# CLK.net
KiCad netlist of a schematic drawn in Altium Designer
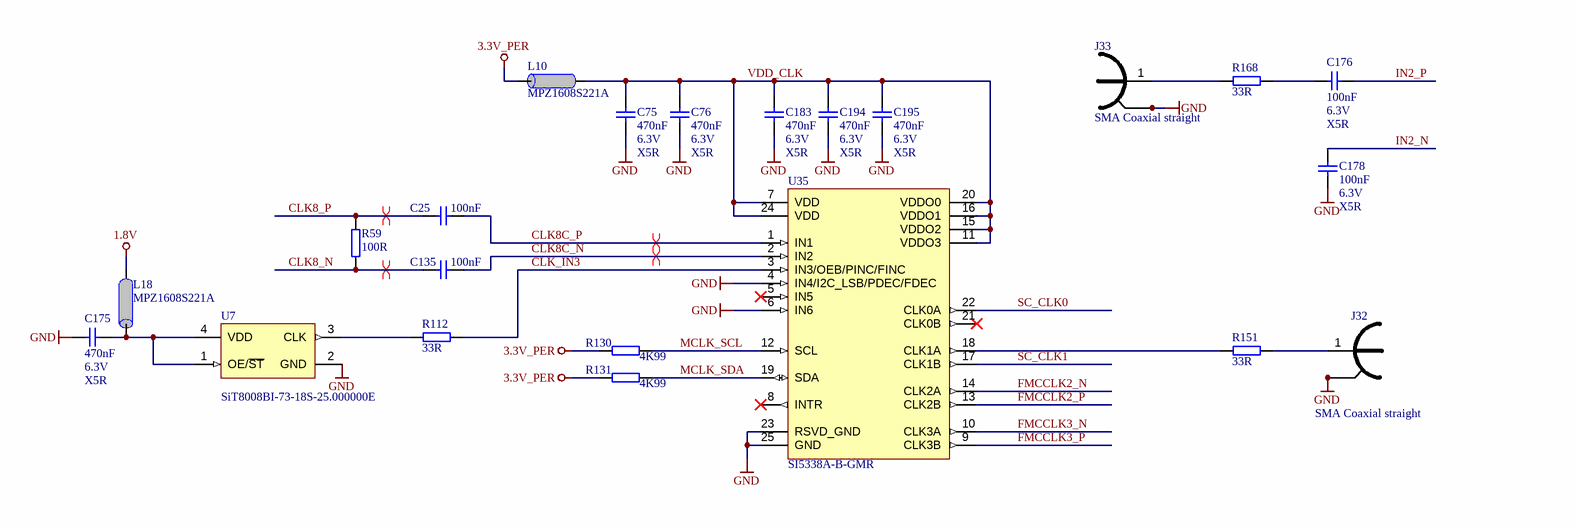
[diagram p0: CLK.schdoc]

(export (version "E")
  (design (tool "Eeschema 10.0.6"))
  (components
    (comp (ref "C25")
      (value "100nF")
      (footprint "CAPC0603X33N")
      (description "KON 100nF 6.3V X5R SMD 10%")
      (fields (field (name "VOLTAGE") "6.3V") (field (name "TOLERANCE") "10%"))
      (libsource (lib "TE") (part "CAP-NP"))
    )
    (comp (ref "C75")
      (value "470nF")
      (footprint "CAPC1005X55N")
      (description "KON 470nF 6,3V X5R SMD")
      (fields (field (name "VOLTAGE") "6.3V") (field (name "TECHNOLOGY") "X5R"))
      (libsource (lib "TE") (part "CAP-NP"))
    )
    (comp (ref "C76")
      (value "470nF")
      (footprint "CAPC1005X55N")
      (description "KON 470nF 6,3V X5R SMD")
      (fields (field (name "VOLTAGE") "6.3V") (field (name "TECHNOLOGY") "X5R"))
      (libsource (lib "TE") (part "CAP-NP"))
    )
    (comp (ref "C135")
      (value "100nF")
      (footprint "CAPC0603X33N")
      (description "KON 100nF 6.3V X5R SMD 10%")
      (fields (field (name "VOLTAGE") "6.3V") (field (name "TOLERANCE") "10%"))
      (libsource (lib "TE") (part "CAP-NP"))
    )
    (comp (ref "C175")
      (value "470nF")
      (footprint "CAPC1005X55N")
      (description "KON 470nF 6,3V X5R SMD")
      (fields (field (name "VOLTAGE") "6.3V") (field (name "TECHNOLOGY") "X5R"))
      (libsource (lib "TE") (part "CAP-NP"))
    )
    (comp (ref "C176")
      (value "100nF")
      (footprint "CAPC0603X33N")
      (description "KON 100nF 6.3V X5R SMD 10%")
      (fields
        (field (name "VOLTAGE") "6.3V")
        (field (name "TECHNOLOGY") "X5R")
        (field (name "TOLERANCE") "10%")
      )
      (libsource (lib "TE") (part "CAP-NP"))
    )
    (comp (ref "C178")
      (value "100nF")
      (footprint "CAPC0603X33N")
      (description "KON 100nF 6.3V X5R SMD 10%")
      (fields
        (field (name "VOLTAGE") "6.3V")
        (field (name "TECHNOLOGY") "X5R")
        (field (name "TOLERANCE") "10%")
      )
      (libsource (lib "TE") (part "CAP-NP"))
    )
    (comp (ref "C183")
      (value "470nF")
      (footprint "CAPC1005X55N")
      (description "KON 470nF 6,3V X5R SMD")
      (fields (field (name "VOLTAGE") "6.3V") (field (name "TECHNOLOGY") "X5R"))
      (libsource (lib "TE") (part "CAP-NP"))
    )
    (comp (ref "C194")
      (value "470nF")
      (footprint "CAPC1005X55N")
      (description "KON 470nF 6,3V X5R SMD")
      (fields (field (name "VOLTAGE") "6.3V") (field (name "TECHNOLOGY") "X5R"))
      (libsource (lib "TE") (part "CAP-NP"))
    )
    (comp (ref "C195")
      (value "470nF")
      (footprint "CAPC1005X55N")
      (description "KON 470nF 6,3V X5R SMD")
      (fields (field (name "VOLTAGE") "6.3V") (field (name "TECHNOLOGY") "X5R"))
      (libsource (lib "TE") (part "CAP-NP"))
    )
    (comp (ref "J32")
      (value "SMA Coaxial straight")
      (footprint "SMA-R125426000")
      (libsource (lib "") (part "SMA_1"))
    )
    (comp (ref "J33")
      (value "SMA Coaxial straight")
      (footprint "SMA-R125426000")
      (libsource (lib "TE") (part "SMA"))
    )
    (comp (ref "L10")
      (value "MPZ1608S221A")
      (footprint "INDC1608X95N")
      (description "Ferritdurchführung MPZ1608S221A")
      (libsource (lib "TE") (part "Ferritperle"))
    )
    (comp (ref "L18")
      (value "MPZ1608S221A")
      (footprint "INDC1608X95N")
      (description "Ferritdurchführung MPZ1608S221A")
      (libsource (lib "") (part "Ferritperle_1"))
    )
    (comp (ref "R59")
      (value "100R")
      (footprint "RESC1005X40N")
      (description "WID SMD 100R 1% 0,063W")
      (fields (field (name "TOLERANCE") "1%"))
      (libsource (lib "TE") (part "RES"))
    )
    (comp (ref "R112")
      (value "33R")
      (footprint "RESC1005X40N")
      (description "WID SMD 33R 1% 0,063W")
      (fields (field (name "TOLERANCE") "1%"))
      (libsource (lib "TE") (part "RES"))
    )
    (comp (ref "R130")
      (value "4K99")
      (footprint "RESC1005X40N")
      (description "WID SMD 4K99 1% 0,063W")
      (fields (field (name "TOLERANCE") "1%"))
      (libsource (lib "TE") (part "RES"))
    )
    (comp (ref "R131")
      (value "4K99")
      (footprint "RESC1005X40N")
      (description "WID SMD 4K99 1% 0,063W")
      (fields (field (name "TOLERANCE") "1%"))
      (libsource (lib "TE") (part "RES"))
    )
    (comp (ref "R151")
      (value "33R")
      (footprint "RESC1005X40N")
      (description "WID SMD 33R 1% 0,063W")
      (fields (field (name "TOLERANCE") "1%"))
      (libsource (lib "TE") (part "RES"))
    )
    (comp (ref "R168")
      (value "33R")
      (footprint "RESC1005X40N")
      (description "WID SMD 33R 1% 0,063W")
      (fields (field (name "TOLERANCE") "1%"))
      (libsource (lib "TE") (part "RES"))
    )
    (comp (ref "U7")
      (value "SiT8008BI-73-18S-25.000000E")
      (footprint "2016")
      (fields (field (name "VOLTAGE") "1.8V"))
      (libsource (lib "TE") (part "SiT8103"))
    )
    (comp (ref "U35")
      (value "SI5338A-B-GMR")
      (footprint "QFN50P400X400X90-25N")
      (description "SI5338A-B-GM")
      (libsource (lib "TE") (part "SI5338A"))
    )
  )
  (nets
    (net (code "1") (name "/CLK8C_N") (class "Default")
      (node (ref "C135") (pin "2") (pinfunction "2_2") (pintype "passive"))
      (node (ref "U35") (pin "2") (pinfunction "IN2_2") (pintype "input"))
    )
    (net (code "2") (name "/CLK8C_P") (class "Default")
      (node (ref "C25") (pin "2") (pinfunction "2_2") (pintype "passive"))
      (node (ref "U35") (pin "1") (pinfunction "IN1_1") (pintype "input"))
    )
    (net (code "3") (name "/CLK8_N") (class "Default")
      (node (ref "C135") (pin "1") (pinfunction "1_1") (pintype "passive"))
      (node (ref "R59") (pin "2") (pinfunction "2_2") (pintype "passive"))
    )
    (net (code "4") (name "/CLK8_P") (class "Default")
      (node (ref "C25") (pin "1") (pinfunction "1_1") (pintype "passive"))
      (node (ref "R59") (pin "1") (pinfunction "1_1") (pintype "passive"))
    )
    (net (code "5") (name "/CLK_IN3") (class "Default")
      (node (ref "R112") (pin "2") (pinfunction "2_2") (pintype "passive"))
      (node (ref "U35") (pin "3") (pinfunction "IN3/OEB/PINC/FINC_3") (pintype "input"))
    )
    (net (code "6") (name "/FMCCLK2_N") (class "Default")
      (node (ref "U35") (pin "14") (pinfunction "CLK2A_14") (pintype "output"))
    )
    (net (code "7") (name "/FMCCLK2_P") (class "Default")
      (node (ref "U35") (pin "13") (pinfunction "CLK2B_13") (pintype "output"))
    )
    (net (code "8") (name "/FMCCLK3_N") (class "Default")
      (node (ref "U35") (pin "10") (pinfunction "CLK3A_10") (pintype "output"))
    )
    (net (code "9") (name "/FMCCLK3_P") (class "Default")
      (node (ref "U35") (pin "9") (pinfunction "CLK3B_9") (pintype "output"))
    )
    (net (code "10") (name "/IN2_N") (class "Default")
      (node (ref "C178") (pin "2") (pinfunction "2_2") (pintype "passive"))
    )
    (net (code "11") (name "/IN2_P") (class "Default")
      (node (ref "C176") (pin "1") (pinfunction "1_1") (pintype "passive"))
    )
    (net (code "12") (name "/MCLK_SCL") (class "Default")
      (node (ref "R130") (pin "2") (pinfunction "2_2") (pintype "passive"))
      (node (ref "U35") (pin "12") (pinfunction "SCL_12") (pintype "input"))
    )
    (net (code "13") (name "/MCLK_SDA") (class "Default")
      (node (ref "R131") (pin "2") (pinfunction "2_2") (pintype "passive"))
      (node (ref "U35") (pin "19") (pinfunction "SDA_19") (pintype "bidirectional"))
    )
    (net (code "14") (name "/SC_CLK0") (class "Default")
      (node (ref "U35") (pin "22") (pinfunction "CLK0A_22") (pintype "output"))
    )
    (net (code "15") (name "/SC_CLK1") (class "Default")
      (node (ref "U35") (pin "17") (pinfunction "CLK1B_17") (pintype "output"))
    )
    (net (code "16") (name "/VDD_CLK") (class "Default")
      (node (ref "C183") (pin "1") (pinfunction "1_1") (pintype "passive"))
      (node (ref "C194") (pin "1") (pinfunction "1_1") (pintype "passive"))
      (node (ref "C195") (pin "1") (pinfunction "1_1") (pintype "passive"))
      (node (ref "C75") (pin "1") (pinfunction "1_1") (pintype "passive"))
      (node (ref "C76") (pin "1") (pinfunction "1_1") (pintype "passive"))
      (node (ref "L10") (pin "1") (pinfunction "1_1") (pintype "passive"))
      (node (ref "U35") (pin "11") (pinfunction "VDDO3_11") (pintype "power_in"))
      (node (ref "U35") (pin "15") (pinfunction "VDDO2_15") (pintype "power_in"))
      (node (ref "U35") (pin "16") (pinfunction "VDDO1_16") (pintype "power_in"))
      (node (ref "U35") (pin "20") (pinfunction "VDDO0_20") (pintype "power_in"))
      (node (ref "U35") (pin "24") (pinfunction "VDD_24") (pintype "power_in"))
      (node (ref "U35") (pin "7") (pinfunction "VDD_7") (pintype "power_in"))
    )
    (net (code "17") (name "1.8V") (class "Default")
      (node (ref "L18") (pin "1") (pinfunction "1_1") (pintype "passive"))
    )
    (net (code "18") (name "3.3V_PER") (class "Default")
      (node (ref "L10") (pin "2") (pinfunction "2_2") (pintype "passive"))
      (node (ref "R130") (pin "1") (pinfunction "1_1") (pintype "passive"))
      (node (ref "R131") (pin "1") (pinfunction "1_1") (pintype "passive"))
    )
    (net (code "19") (name "GND") (class "Default")
      (node (ref "C175") (pin "2") (pinfunction "2_2") (pintype "passive"))
      (node (ref "C178") (pin "1") (pinfunction "1_1") (pintype "passive"))
      (node (ref "C183") (pin "2") (pinfunction "2_2") (pintype "passive"))
      (node (ref "C194") (pin "2") (pinfunction "2_2") (pintype "passive"))
      (node (ref "C195") (pin "2") (pinfunction "2_2") (pintype "passive"))
      (node (ref "C75") (pin "2") (pinfunction "2_2") (pintype "passive"))
      (node (ref "C76") (pin "2") (pinfunction "2_2") (pintype "passive"))
      (node (ref "J32") (pin "2") (pinfunction "2_2") (pintype "passive"))
      (node (ref "J32") (pin "3") (pinfunction "3_3") (pintype "passive"))
      (node (ref "J32") (pin "4") (pinfunction "4_4") (pintype "passive"))
      (node (ref "J32") (pin "5") (pinfunction "5_5") (pintype "passive"))
      (node (ref "J33") (pin "2") (pinfunction "2_2") (pintype "passive"))
      (node (ref "J33") (pin "3") (pinfunction "3_3") (pintype "passive"))
      (node (ref "J33") (pin "4") (pinfunction "4_4") (pintype "passive"))
      (node (ref "J33") (pin "5") (pinfunction "5_5") (pintype "passive"))
      (node (ref "U35") (pin "23") (pinfunction "RSVD_GND_23") (pintype "power_in"))
      (node (ref "U35") (pin "25") (pinfunction "GND_25") (pintype "power_in"))
      (node (ref "U35") (pin "4") (pinfunction "IN4/I2C_LSB/PDEC/FDEC_4") (pintype "input"))
      (node (ref "U35") (pin "6") (pinfunction "IN6_6") (pintype "input"))
      (node (ref "U7") (pin "2") (pinfunction "GND_2") (pintype "power_in"))
    )
    (net (code "20") (name "Net-(C176-Pad2)") (class "Default")
      (node (ref "C176") (pin "2") (pinfunction "2_2") (pintype "passive"))
      (node (ref "R168") (pin "2") (pinfunction "2_2") (pintype "passive"))
    )
    (net (code "21") (name "Net-(J32-Pad1)") (class "Default")
      (node (ref "J32") (pin "1") (pinfunction "1_1") (pintype "passive"))
      (node (ref "R151") (pin "2") (pinfunction "2_2") (pintype "passive"))
    )
    (net (code "22") (name "Net-(J33-Pad1)") (class "Default")
      (node (ref "J33") (pin "1") (pinfunction "1_1") (pintype "passive"))
      (node (ref "R168") (pin "1") (pinfunction "1_1") (pintype "passive"))
    )
    (net (code "23") (name "Net-(U7-CLK)") (class "Default")
      (node (ref "R112") (pin "1") (pinfunction "1_1") (pintype "passive"))
      (node (ref "U7") (pin "3") (pinfunction "CLK_3") (pintype "output"))
    )
    (net (code "24") (name "Net-(U7-OE{slash}~{ST})") (class "Default")
      (node (ref "C175") (pin "1") (pinfunction "1_1") (pintype "passive"))
      (node (ref "L18") (pin "2") (pinfunction "2_2") (pintype "passive"))
      (node (ref "U7") (pin "1") (pinfunction "OE/~{ST}_1") (pintype "input"))
      (node (ref "U7") (pin "4") (pinfunction "VDD_4") (pintype "power_in"))
    )
    (net (code "25") (name "Net-(U35-CLK1A)") (class "Default")
      (node (ref "R151") (pin "1") (pinfunction "1_1") (pintype "passive"))
      (node (ref "U35") (pin "18") (pinfunction "CLK1A_18") (pintype "output"))
    )
    (net (code "26") (name "unconnected-(U35-CLK0B-Pad21)") (class "Default")
      (node (ref "U35") (pin "21") (pinfunction "CLK0B_21") (pintype "output+no_connect"))
    )
    (net (code "27") (name "unconnected-(U35-IN5-Pad5)") (class "Default")
      (node (ref "U35") (pin "5") (pinfunction "IN5_5") (pintype "input+no_connect"))
    )
    (net (code "28") (name "unconnected-(U35-INTR-Pad8)") (class "Default")
      (node (ref "U35") (pin "8") (pinfunction "INTR_8") (pintype "output+no_connect"))
    )
  )
)
